# Regulator.net
KiCad netlist of a schematic drawn in Altium Designer
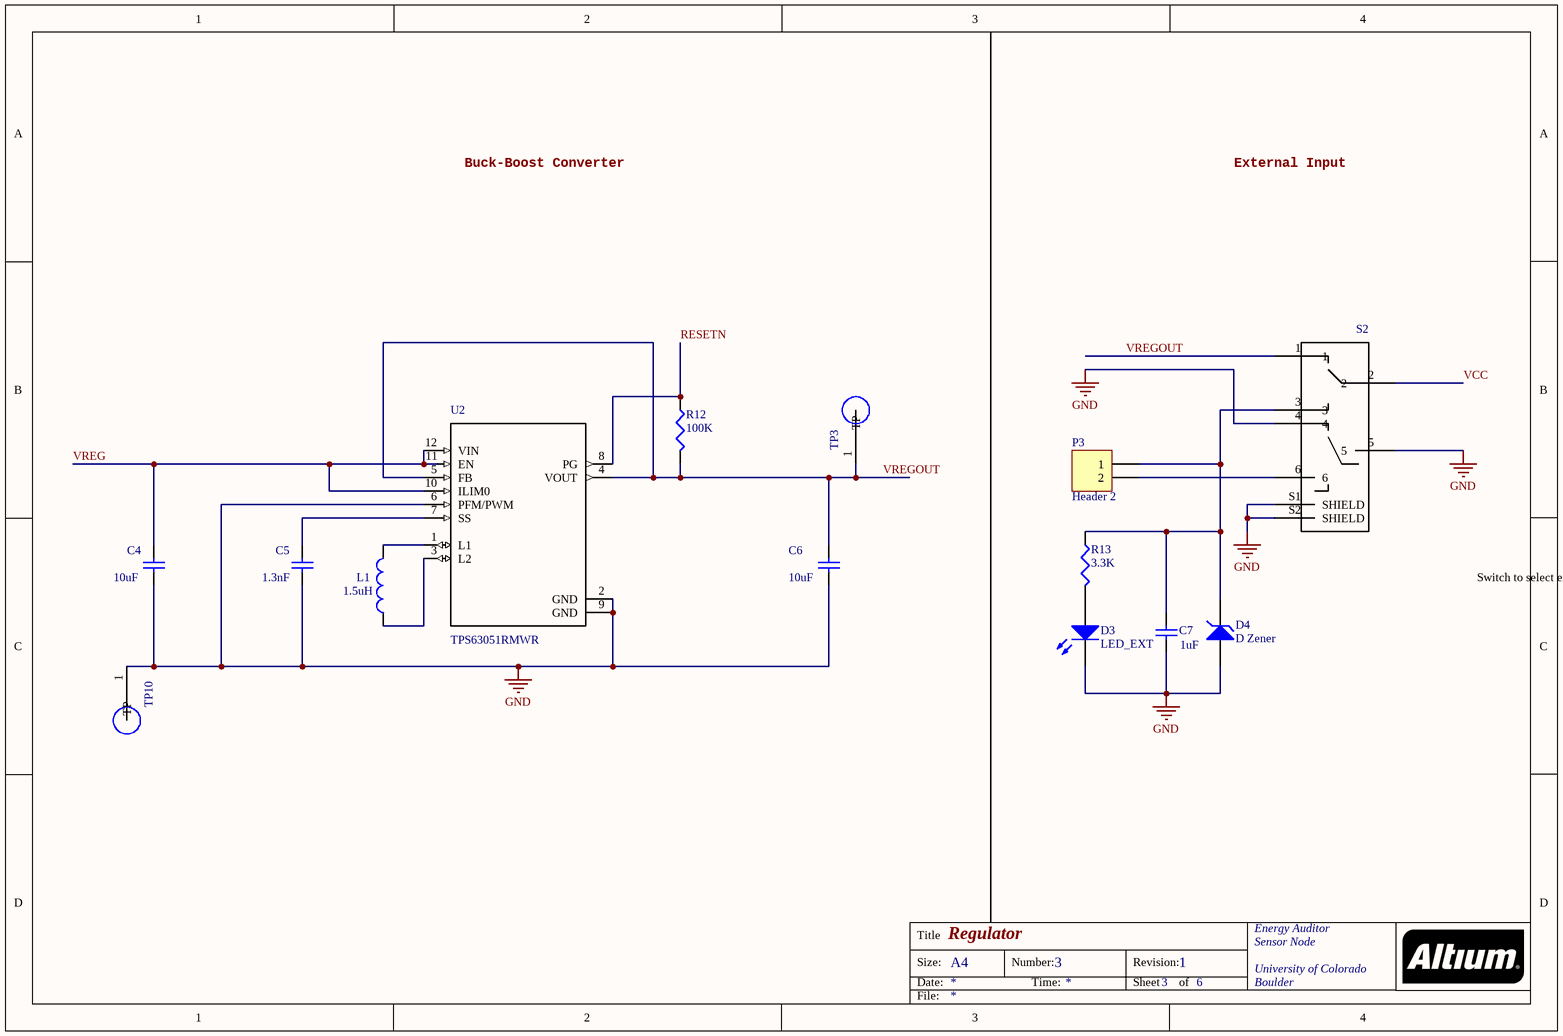
[diagram p0: Regulator.SchDoc]

(export (version "E")
  (design (tool "Eeschema 10.0.6"))
  (components
    (comp (ref "C4")
      (value "10uF")
      (footprint "1608[0603]")
      (description "CAP CER 10UF 10V X5R 0603")
      (fields
        (field (name "MANUFACTURER") "Murata Electronics North America")
        (field (name "MANUFACTURER PART NUMBER") "GRM188R61A106KE69D")
      )
      (libsource (lib "Miscellaneous Devices") (part "Cap"))
    )
    (comp (ref "C5")
      (value "1.3nF")
      (footprint "1608[0603]")
      (description "CAP CER 1300PF 25V C0G/NP0 0603")
      (fields
        (field (name "MANUFACTURER") "KEMET")
        (field (name "MANUFACTURER PART NUMBER") "C0603C132J3GAC7867")
      )
      (libsource (lib "Miscellaneous Devices") (part "Cap"))
    )
    (comp (ref "C6")
      (value "10uF")
      (footprint "1608[0603]")
      (description "CAP CER 10UF 10V X5R 0603")
      (fields
        (field (name "MANUFACTURER") "Murata Electronics North America")
        (field (name "MANUFACTURER PART NUMBER") "GRM188R61A106KE69D")
      )
      (libsource (lib "Miscellaneous Devices") (part "Cap"))
    )
    (comp (ref "C7")
      (value "1uF")
      (footprint "1608[0603]")
      (description "CAP CER 1UF 16V X7R 0603")
      (fields
        (field (name "DIGI-KEY PART NUMBER") "1276-6524-1-ND")
        (field (name "MANUFACTURER") "Samsung Electro-Mechanics")
      )
      (libsource (lib "Miscellaneous Devices") (part "Cap"))
    )
    (comp (ref "D3")
      (value "LED_EXT")
      (footprint "3.2X1.6X1.1")
      (description "LED GREEN DIFFUSED 0603 SMD")
      (fields
        (field (name "DIGI-KEY PART NUMBER") "475-3118-1-ND")
        (field (name "MANUFACTURER") "OSRAM Opto Semiconductors Inc.")
      )
      (libsource (lib "Miscellaneous Devices") (part "LED2"))
    )
    (comp (ref "D4")
      (value "D Zener")
      (footprint "0402")
      (description "TVS DIODE 5.5V 14V 2X1SON")
      (fields
        (field (name "MANUFACTURER PART NUMBER") "TPD1E10B06DPYR")
        (field (name "DIGI-KEY PART NUMBER") "296-30406-1-ND")
      )
      (libsource (lib "Miscellaneous Devices") (part "D Zener"))
    )
    (comp (ref "L1")
      (value "1.5uH")
      (footprint "0603")
      (description "FIXED IND 1.5UH 1.1A 213 MOHM")
      (fields
        (field (name "MANUFACTURER") "Murata Electronics North America")
        (field (name "MANUFACTURER PART NUMBER") "LQM18PN1R5MFHD")
      )
      (libsource (lib "Miscellaneous Devices") (part "Inductor"))
    )
    (comp (ref "P3")
      (value "Header 2")
      (footprint "HDR1X2")
      (description "Header, 2-Pin")
      (libsource (lib "Miscellaneous Connectors") (part "Header 2"))
    )
    (comp (ref "R12")
      (value "100K")
      (footprint "1608[0603]")
      (description "RES SMD 100K OHM 0.1% 1/10W 0603")
      (fields
        (field (name "MANUFACTURER") "Susumu")
        (field (name "MANUFACTURER PART NUMBER") "RG1608P-104-B-T5")
      )
      (libsource (lib "Miscellaneous Devices") (part "Res3"))
    )
    (comp (ref "R13")
      (value "3.3K")
      (footprint "1608[0603]")
      (description "RES SMD 3.3K OHM 5% 1/10W 0603")
      (fields
        (field (name "DIGI-KEY PART NUMBER") "P3.3KGCT-ND")
        (field (name "MANUFACTURER") "Panasonic Electronic Components")
      )
      (libsource (lib "Miscellaneous Devices") (part "Res3"))
    )
    (comp (ref "S2")
      (value "1825289-1")
      (footprint "SW_1825289-1_1825289-1(Primary)")
      (description "MHS22204=DPDT SL SW VERT AG")
      (fields
        (field (name "MANUFACTURER") "TE Connectivity")
        (field (name "DIGI-KEY PART NUMBER") "450-1572-ND")
      )
      (libsource (lib "1825289-1") (part "1825289-1"))
    )
    (comp (ref "TP3")
      (value "5019")
      (footprint "TP380X203")
      (description "Phosphor Bronze Contact Miniature Silver Plated Surface Mount Test Points")
      (fields (field (name "DIGI-KEY PART NUMBER") "36-5019CT-ND") (field (name "MANUFACTURER") "Keystone"))
      (libsource (lib "5019") (part "5019"))
    )
    (comp (ref "TP10")
      (value "5019")
      (footprint "TP380X203")
      (description "Phosphor Bronze Contact Miniature Silver Plated Surface Mount Test Points")
      (fields (field (name "DIGI-KEY PART NUMBER") "36-5019CT-ND") (field (name "MANUFACTURER") "Keystone"))
      (libsource (lib "5019") (part "5019"))
    )
    (comp (ref "U2")
      (value "TPS63051RMWR")
      (footprint "QFN50P250X250X100-12N")
      (description "Tiny Single Inductor Buck Boost Converter 12-VQFN -40 to 85")
      (fields
        (field (name "MANUFACTURER") "Texas Instruments")
        (field (name "DIGI-KEY PART NUMBER") "296-42650-1-ND")
      )
      (libsource (lib "TPS63051RMWR") (part "TPS63051RMWR"))
    )
  )
  (nets
    (net (code "1") (name "/RESETN") (class "Default")
      (node (ref "R12") (pin "1") (pinfunction "1_1") (pintype "passive"))
      (node (ref "U2") (pin "8") (pinfunction "PG_8") (pintype "output"))
    )
    (net (code "2") (name "/VCC") (class "Default")
      (node (ref "S2") (pin "2") (pinfunction "2_2") (pintype "passive"))
    )
    (net (code "3") (name "/VREG") (class "Default")
      (node (ref "C4") (pin "2") (pinfunction "2_2") (pintype "passive"))
      (node (ref "U2") (pin "10") (pinfunction "ILIM0_10") (pintype "input"))
      (node (ref "U2") (pin "11") (pinfunction "EN_11") (pintype "input"))
      (node (ref "U2") (pin "12") (pinfunction "VIN_12") (pintype "input"))
    )
    (net (code "4") (name "/VREGOUT") (class "Default")
      (node (ref "C6") (pin "2") (pinfunction "2_2") (pintype "passive"))
      (node (ref "R12") (pin "2") (pinfunction "2_2") (pintype "passive"))
      (node (ref "S2") (pin "1") (pinfunction "1_1") (pintype "passive"))
      (node (ref "TP3") (pin "1") (pinfunction "TP_1") (pintype "passive"))
      (node (ref "U2") (pin "4") (pinfunction "VOUT_4") (pintype "output"))
      (node (ref "U2") (pin "5") (pinfunction "FB_5") (pintype "input"))
    )
    (net (code "5") (name "GND") (class "Default")
      (node (ref "C4") (pin "1") (pinfunction "1_1") (pintype "passive"))
      (node (ref "C5") (pin "1") (pinfunction "1_1") (pintype "passive"))
      (node (ref "C6") (pin "1") (pinfunction "1_1") (pintype "passive"))
      (node (ref "C7") (pin "1") (pinfunction "1_1") (pintype "passive"))
      (node (ref "D3") (pin "2") (pinfunction "K_2") (pintype "passive"))
      (node (ref "D4") (pin "1") (pinfunction "A_1") (pintype "passive"))
      (node (ref "S2") (pin "4") (pinfunction "4_4") (pintype "passive"))
      (node (ref "S2") (pin "5") (pinfunction "5_5") (pintype "passive"))
      (node (ref "S2") (pin "S1") (pinfunction "SHIELD_S1") (pintype "passive"))
      (node (ref "S2") (pin "S2") (pinfunction "SHIELD_S2") (pintype "passive"))
      (node (ref "TP10") (pin "1") (pinfunction "TP_1") (pintype "passive"))
      (node (ref "U2") (pin "2") (pinfunction "GND_2") (pintype "power_in"))
      (node (ref "U2") (pin "6") (pinfunction "PFM/PWM_6") (pintype "input"))
      (node (ref "U2") (pin "9") (pinfunction "GND_9") (pintype "power_in"))
    )
    (net (code "6") (name "Net-(D3-A)") (class "Default")
      (node (ref "D3") (pin "1") (pinfunction "A_1") (pintype "passive"))
      (node (ref "R13") (pin "1") (pinfunction "1_1") (pintype "passive"))
    )
    (net (code "7") (name "Net-(D4-K)") (class "Default")
      (node (ref "C7") (pin "2") (pinfunction "2_2") (pintype "passive"))
      (node (ref "D4") (pin "2") (pinfunction "K_2") (pintype "passive"))
      (node (ref "P3") (pin "1") (pinfunction "1_1") (pintype "passive"))
      (node (ref "R13") (pin "2") (pinfunction "2_2") (pintype "passive"))
      (node (ref "S2") (pin "3") (pinfunction "3_3") (pintype "passive"))
    )
    (net (code "8") (name "Net-(P3-Pad2)") (class "Default")
      (node (ref "P3") (pin "2") (pinfunction "2_2") (pintype "passive"))
      (node (ref "S2") (pin "6") (pinfunction "6_6") (pintype "passive"))
    )
    (net (code "9") (name "Net-(U2-L1)") (class "Default")
      (node (ref "L1") (pin "2") (pinfunction "2_2") (pintype "passive"))
      (node (ref "U2") (pin "1") (pinfunction "L1_1") (pintype "bidirectional"))
    )
    (net (code "10") (name "Net-(U2-L2)") (class "Default")
      (node (ref "L1") (pin "1") (pinfunction "1_1") (pintype "passive"))
      (node (ref "U2") (pin "3") (pinfunction "L2_3") (pintype "bidirectional"))
    )
    (net (code "11") (name "Net-(U2-SS)") (class "Default")
      (node (ref "C5") (pin "2") (pinfunction "2_2") (pintype "passive"))
      (node (ref "U2") (pin "7") (pinfunction "SS_7") (pintype "input"))
    )
  )
)
